# Trampoline_Light_Control_Breakout.net
KiCad netlist of a schematic drawn in EAGLE
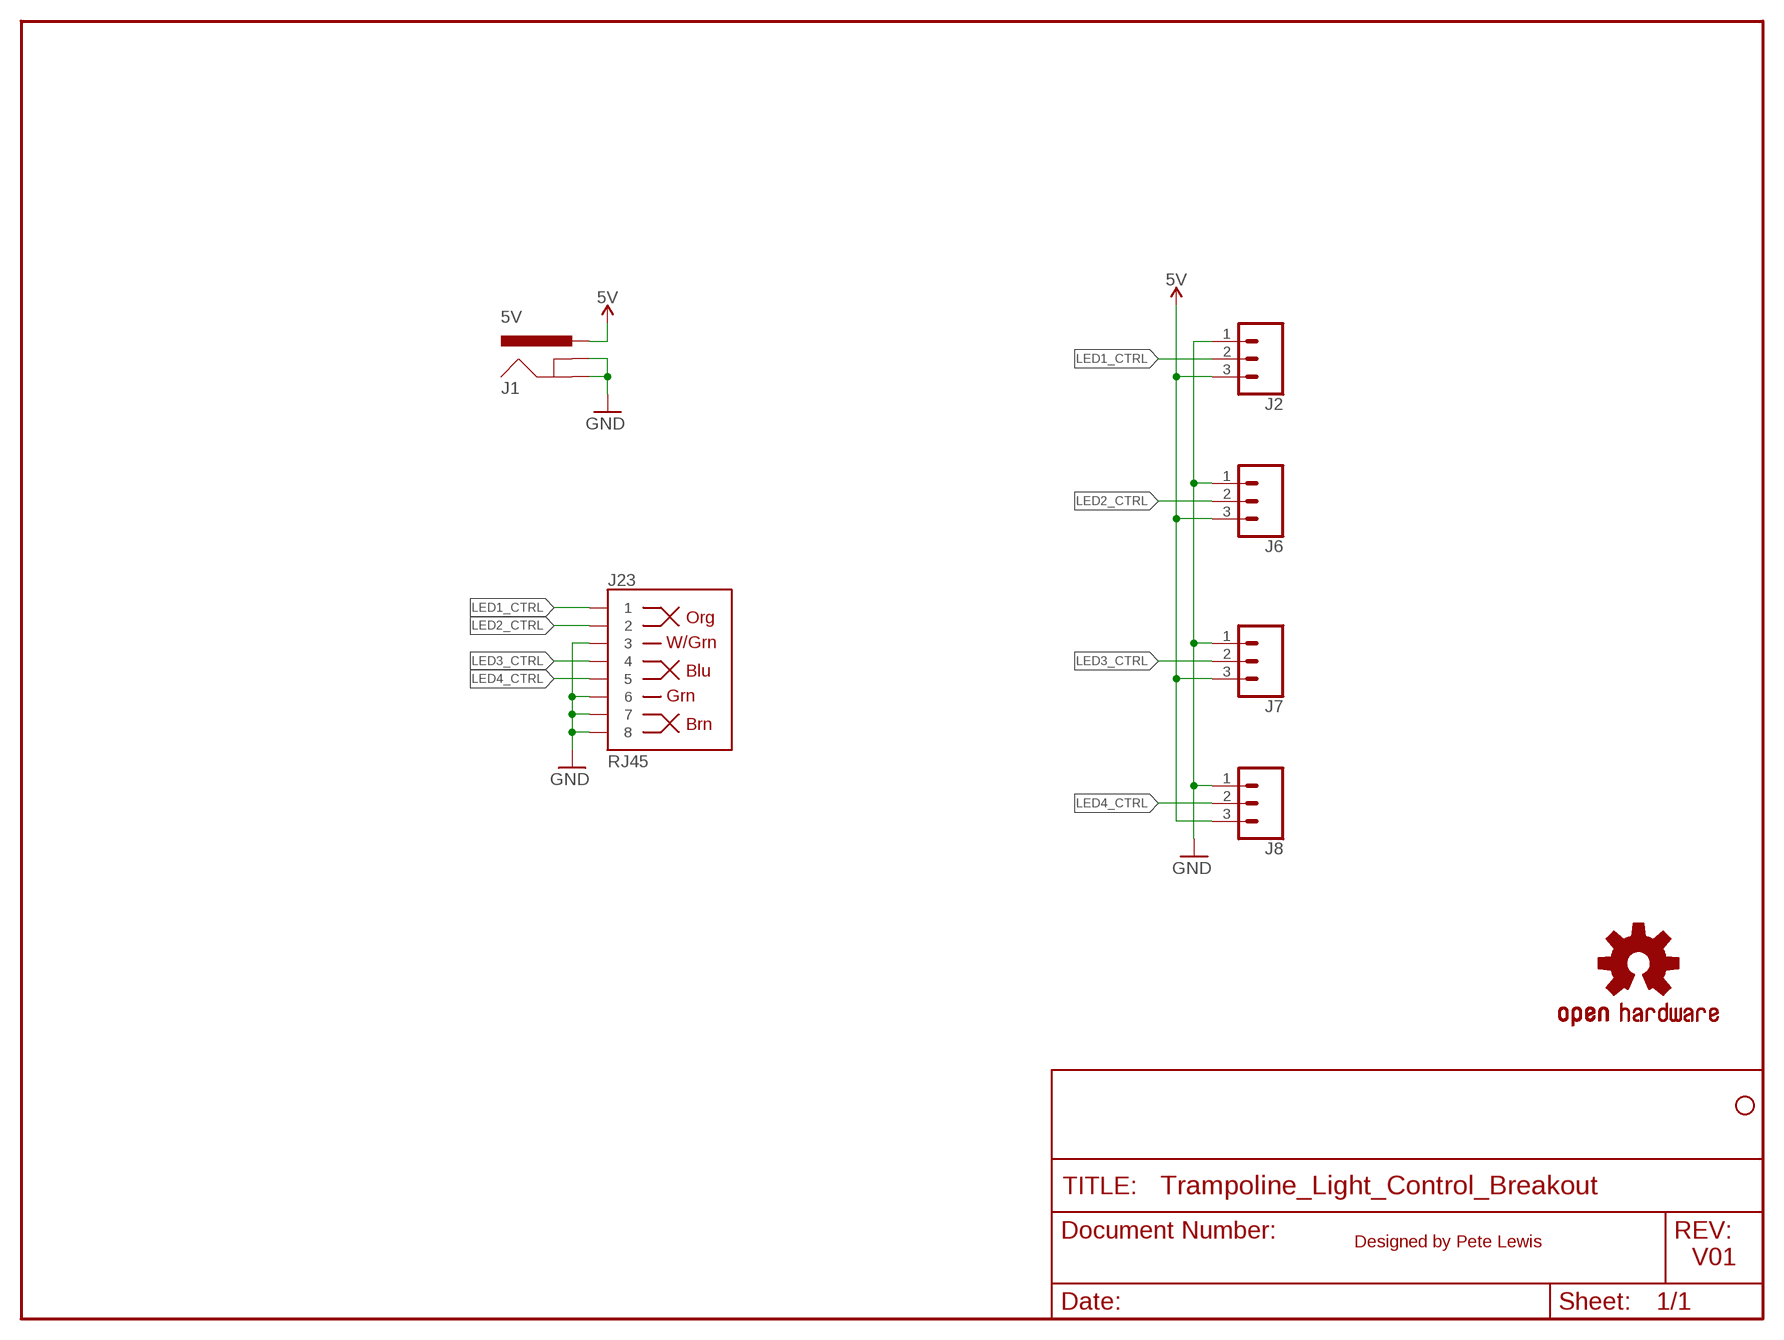
[diagram p0: schematic, sheet 1]

(export (version "E")
  (design (tool "Eeschema 10.0.6"))
  (components
    (comp (ref "J1")
      (value "5V")
      (footprint "eagle-import:POWER_JACK_PTH_LOCK")
      (libsource (lib "eagle-import") (part "POWER_JACKPTH_LOCK"))
    )
    (comp (ref "J2")
      (value "CONN_03LONGPADS")
      (footprint "eagle-import:1X03_LONGPADS")
      (libsource (lib "eagle-import") (part "CONN_03LONGPADS"))
    )
    (comp (ref "J6")
      (value "CONN_03LONGPADS")
      (footprint "eagle-import:1X03_LONGPADS")
      (libsource (lib "eagle-import") (part "CONN_03LONGPADS"))
    )
    (comp (ref "J7")
      (value "CONN_03LONGPADS")
      (footprint "eagle-import:1X03_LONGPADS")
      (libsource (lib "eagle-import") (part "CONN_03LONGPADS"))
    )
    (comp (ref "J8")
      (value "CONN_03LONGPADS")
      (footprint "eagle-import:1X03_LONGPADS")
      (libsource (lib "eagle-import") (part "CONN_03LONGPADS"))
    )
    (comp (ref "J23")
      (value "RJ45")
      (footprint "eagle-import:RJ45-8")
      (libsource (lib "eagle-import") (part "RJ45-8"))
    )
    (comp (ref "JP1")
      (value "STAND-OFFTIGHTER")
      (footprint "eagle-import:STAND-OFF-TIGHTER")
      (libsource (lib "eagle-import") (part "STAND-OFFTIGHTER"))
    )
    (comp (ref "LOGO2")
      (value "OSHW-LOGOS")
      (footprint "eagle-import:OSHW-LOGO-S")
      (libsource (lib "eagle-import") (part "OSHW-LOGOS"))
    )
  )
  (nets
    (net (code "1") (name "5V") (class "Default")
      (node (ref "J1") (pin "PWR") (pinfunction "PWR_PWR") (pintype "bidirectional"))
      (node (ref "J2") (pin "3") (pinfunction "3_3") (pintype "passive"))
      (node (ref "J6") (pin "3") (pinfunction "3_3") (pintype "passive"))
      (node (ref "J7") (pin "3") (pinfunction "3_3") (pintype "passive"))
      (node (ref "J8") (pin "3") (pinfunction "3_3") (pintype "passive"))
    )
    (net (code "2") (name "GND") (class "Default")
      (node (ref "J1") (pin "GND") (pinfunction "GND_GND") (pintype "bidirectional"))
      (node (ref "J1") (pin "GNDBREAK") (pinfunction "GNDBREAK_GNDBREAK") (pintype "bidirectional"))
      (node (ref "J2") (pin "1") (pinfunction "1_1") (pintype "passive"))
      (node (ref "J23") (pin "3") (pinfunction "3_3") (pintype "bidirectional"))
      (node (ref "J23") (pin "6") (pinfunction "6_6") (pintype "bidirectional"))
      (node (ref "J23") (pin "7") (pinfunction "7_7") (pintype "bidirectional"))
      (node (ref "J23") (pin "8") (pinfunction "8_8") (pintype "bidirectional"))
      (node (ref "J6") (pin "1") (pinfunction "1_1") (pintype "passive"))
      (node (ref "J7") (pin "1") (pinfunction "1_1") (pintype "passive"))
      (node (ref "J8") (pin "1") (pinfunction "1_1") (pintype "passive"))
    )
    (net (code "3") (name "LED1_CTRL") (class "Default")
      (node (ref "J2") (pin "2") (pinfunction "2_2") (pintype "passive"))
      (node (ref "J23") (pin "1") (pinfunction "1_1") (pintype "bidirectional"))
    )
    (net (code "4") (name "LED2_CTRL") (class "Default")
      (node (ref "J23") (pin "2") (pinfunction "2_2") (pintype "bidirectional"))
      (node (ref "J6") (pin "2") (pinfunction "2_2") (pintype "passive"))
    )
    (net (code "5") (name "LED3_CTRL") (class "Default")
      (node (ref "J23") (pin "4") (pinfunction "4_4") (pintype "bidirectional"))
      (node (ref "J7") (pin "2") (pinfunction "2_2") (pintype "passive"))
    )
    (net (code "6") (name "LED4_CTRL") (class "Default")
      (node (ref "J23") (pin "5") (pinfunction "5_5") (pintype "bidirectional"))
      (node (ref "J8") (pin "2") (pinfunction "2_2") (pintype "passive"))
    )
  )
)
